# Design.net
KiCad netlist of a schematic drawn in Altium Designer
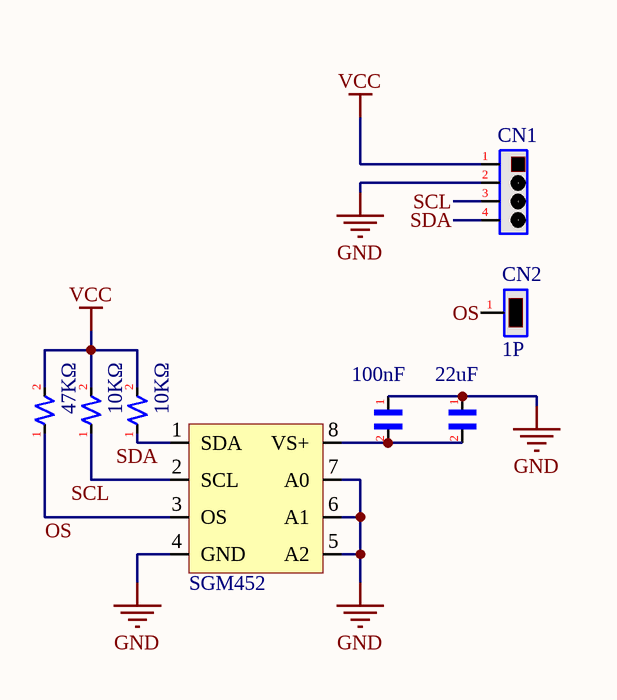
[diagram p0: Design.SchDoc]

(export (version "E")
  (design (tool "Eeschema 10.0.6"))
  (components
    (comp (ref "C1")
      (value "100nF")
      (footprint "C_0603")
      (libsource (lib "Walton_EED") (part "Capacitor{gt}{gt} Non-Polar"))
    )
    (comp (ref "C2")
      (value "22uF")
      (footprint "C_0603")
      (libsource (lib "Walton_EED") (part "Capacitor{gt}{gt} Non-Polar"))
    )
    (comp (ref "CN1")
      (value "~")
      (footprint "CN_4P_A2001WV-XP-180DEG")
      (libsource (lib "Walton_EED") (part "Connector{gt}{gt} 4Pins"))
    )
    (comp (ref "CN2")
      (value "1P")
      (footprint "CN_Ø1.25mm_Lead")
      (libsource (lib "Walton_EED") (part "Connector{gt}{gt} 1Pin"))
    )
    (comp (ref "R1")
      (value "47KΩ")
      (footprint "R_0603")
      (libsource (lib "Walton_EED") (part "Resistor{gt}{gt} General Purpose"))
    )
    (comp (ref "R2")
      (value "10KΩ")
      (footprint "R_0603")
      (libsource (lib "Walton_EED") (part "Resistor{gt}{gt} General Purpose"))
    )
    (comp (ref "R3")
      (value "10KΩ")
      (footprint "R_0603")
      (libsource (lib "Walton_EED") (part "Resistor{gt}{gt} General Purpose"))
    )
    (comp (ref "SGM1")
      (value "SGM452")
      (footprint "SGM452-TSOP65P490X110-8N")
      (description "SGM452\r\nDigital Temperature Sensor and\r\nThermal Watchdog with Two-Wire Interface")
      (libsource (lib "PCB_LIB_ENG_SHOHAN") (part "SGM452"))
    )
  )
  (nets
    (net (code "2") (name "/OS") (class "Default")
      (node (ref "CN2") (pin "1") (pinfunction "1_1") (pintype "passive"))
      (node (ref "R1") (pin "1") (pinfunction "1_1") (pintype "passive"))
      (node (ref "SGM1") (pin "3") (pinfunction "OS_3") (pintype "passive"))
    )
    (net (code "3") (name "/SCL") (class "Default")
      (node (ref "CN1") (pin "3") (pinfunction "3_3") (pintype "passive"))
      (node (ref "R2") (pin "1") (pinfunction "1_1") (pintype "passive"))
      (node (ref "SGM1") (pin "2") (pinfunction "SCL_2") (pintype "passive"))
    )
    (net (code "4") (name "/SDA") (class "Default")
      (node (ref "CN1") (pin "4") (pinfunction "4_4") (pintype "passive"))
      (node (ref "R3") (pin "1") (pinfunction "1_1") (pintype "passive"))
      (node (ref "SGM1") (pin "1") (pinfunction "SDA_1") (pintype "passive"))
    )
    (net (code "5") (name "GND") (class "Default")
      (node (ref "C1") (pin "1") (pinfunction "1_1") (pintype "passive"))
      (node (ref "C2") (pin "1") (pinfunction "1_1") (pintype "passive"))
      (node (ref "CN1") (pin "2") (pinfunction "2_2") (pintype "passive"))
      (node (ref "SGM1") (pin "4") (pinfunction "GND_4") (pintype "power_in"))
      (node (ref "SGM1") (pin "5") (pinfunction "A2_5") (pintype "passive"))
      (node (ref "SGM1") (pin "6") (pinfunction "A1_6") (pintype "passive"))
      (node (ref "SGM1") (pin "7") (pinfunction "A0_7") (pintype "passive"))
    )
    (net (code "6") (name "Net-(SGM1-VS+)") (class "Default")
      (node (ref "C1") (pin "2") (pinfunction "2_2") (pintype "passive"))
      (node (ref "C2") (pin "2") (pinfunction "2_2") (pintype "passive"))
      (node (ref "SGM1") (pin "8") (pinfunction "VS+_8") (pintype "power_in"))
    )
    (net (code "7") (name "VCC") (class "Default")
      (node (ref "CN1") (pin "1") (pinfunction "1_1") (pintype "passive"))
      (node (ref "R1") (pin "2") (pinfunction "2_2") (pintype "passive"))
      (node (ref "R2") (pin "2") (pinfunction "2_2") (pintype "passive"))
      (node (ref "R3") (pin "2") (pinfunction "2_2") (pintype "passive"))
    )
  )
)
